# sch_substrate_board_isp.net
KiCad netlist of a schematic drawn in Altium Designer
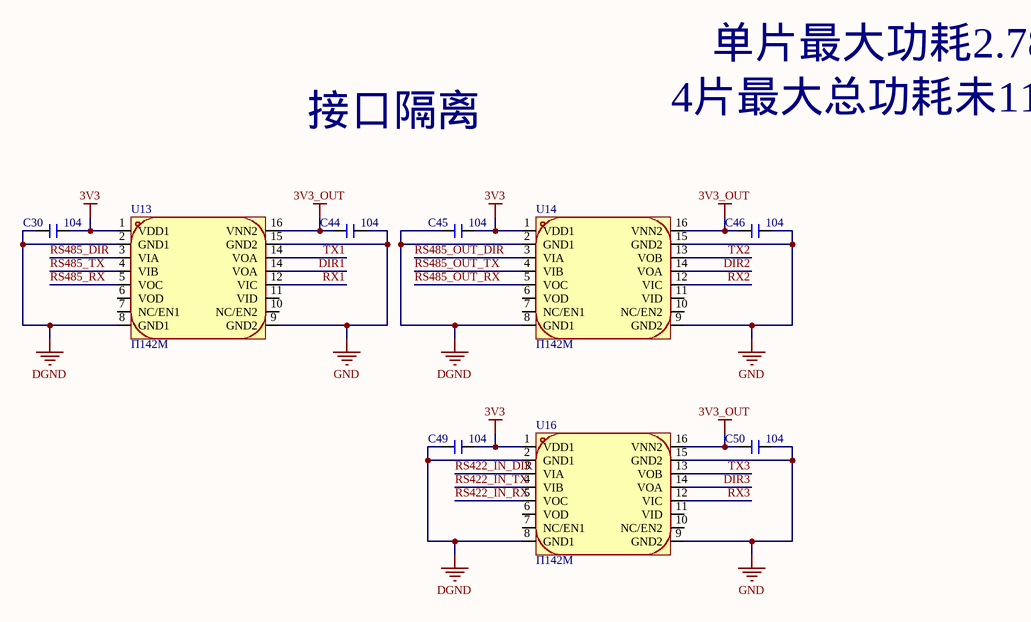
[diagram p0: sch_substrate_board_isp.SchDoc]

(export (version "E")
  (design (tool "Eeschema 10.0.6"))
  (components
    (comp (ref "C30")
      (value "104")
      (footprint "C 0805_L")
      (description "贴片电容")
      (libsource (lib "0.1 - 电阻-电容-电感") (part "C"))
    )
    (comp (ref "C44")
      (value "104")
      (footprint "C 0805_L")
      (description "贴片电容")
      (libsource (lib "0.1 - 电阻-电容-电感") (part "C"))
    )
    (comp (ref "C45")
      (value "104")
      (footprint "C 0805_L")
      (description "贴片电容")
      (libsource (lib "0.1 - 电阻-电容-电感") (part "C"))
    )
    (comp (ref "C46")
      (value "104")
      (footprint "C 0805_L")
      (description "贴片电容")
      (libsource (lib "0.1 - 电阻-电容-电感") (part "C"))
    )
    (comp (ref "C49")
      (value "104")
      (footprint "C 0805_L")
      (description "贴片电容")
      (libsource (lib "0.1 - 电阻-电容-电感") (part "C"))
    )
    (comp (ref "C50")
      (value "104")
      (footprint "C 0805_L")
      (description "贴片电容")
      (libsource (lib "0.1 - 电阻-电容-电感") (part "C"))
    )
    (comp (ref "U13")
      (value "Π142M")
      (footprint "π120M32")
      (description "数字隔离器")
      (libsource (lib "") (part "Π142M_1"))
    )
    (comp (ref "U14")
      (value "Π142M")
      (footprint "π120M32")
      (description "数字隔离器")
      (libsource (lib "schlib_substrate") (part "Π142M"))
    )
    (comp (ref "U16")
      (value "Π142M")
      (footprint "π120M32")
      (description "数字隔离器")
      (libsource (lib "schlib_substrate") (part "Π142M"))
    )
  )
  (nets
    (net (code "1") (name "/DIR1") (class "Default")
      (node (ref "U13") (pin "14") (pinfunction "VOA_14") (pintype "passive"))
    )
    (net (code "2") (name "/DIR2") (class "Default")
      (node (ref "U14") (pin "14") (pinfunction "VOA_14") (pintype "passive"))
    )
    (net (code "3") (name "/DIR3") (class "Default")
      (node (ref "U16") (pin "14") (pinfunction "VOA_14") (pintype "passive"))
    )
    (net (code "4") (name "/RS422_IN_DIR") (class "Default")
      (node (ref "U16") (pin "3") (pinfunction "VIA_3") (pintype "passive"))
    )
    (net (code "5") (name "/RS422_IN_RX") (class "Default")
      (node (ref "U16") (pin "5") (pinfunction "VOC_5") (pintype "passive"))
    )
    (net (code "6") (name "/RS422_IN_TX") (class "Default")
      (node (ref "U16") (pin "4") (pinfunction "VIB_4") (pintype "passive"))
    )
    (net (code "7") (name "/RS485_DIR") (class "Default")
      (node (ref "U13") (pin "3") (pinfunction "VIA_3") (pintype "passive"))
    )
    (net (code "8") (name "/RS485_OUT_DIR") (class "Default")
      (node (ref "U14") (pin "3") (pinfunction "VIA_3") (pintype "passive"))
    )
    (net (code "9") (name "/RS485_OUT_RX") (class "Default")
      (node (ref "U14") (pin "5") (pinfunction "VOC_5") (pintype "passive"))
    )
    (net (code "10") (name "/RS485_OUT_TX") (class "Default")
      (node (ref "U14") (pin "4") (pinfunction "VIB_4") (pintype "passive"))
    )
    (net (code "11") (name "/RS485_RX") (class "Default")
      (node (ref "U13") (pin "5") (pinfunction "VOC_5") (pintype "passive"))
    )
    (net (code "12") (name "/RS485_TX") (class "Default")
      (node (ref "U13") (pin "4") (pinfunction "VIB_4") (pintype "passive"))
    )
    (net (code "13") (name "/RX1") (class "Default")
      (node (ref "U13") (pin "12") (pinfunction "VIC_12") (pintype "passive"))
    )
    (net (code "14") (name "/RX2") (class "Default")
      (node (ref "U14") (pin "12") (pinfunction "VIC_12") (pintype "passive"))
    )
    (net (code "15") (name "/RX3") (class "Default")
      (node (ref "U16") (pin "12") (pinfunction "VIC_12") (pintype "passive"))
    )
    (net (code "16") (name "/TX1") (class "Default")
      (node (ref "U13") (pin "14") (pinfunction "VOA_14") (pintype "passive"))
    )
    (net (code "17") (name "/TX2") (class "Default")
      (node (ref "U14") (pin "13") (pinfunction "VOB_13") (pintype "passive"))
    )
    (net (code "18") (name "/TX3") (class "Default")
      (node (ref "U16") (pin "13") (pinfunction "VOB_13") (pintype "passive"))
    )
    (net (code "19") (name "3V3") (class "Default")
      (node (ref "C30") (pin "1") (pinfunction "1_1") (pintype "passive"))
      (node (ref "C45") (pin "1") (pinfunction "1_1") (pintype "passive"))
      (node (ref "C49") (pin "1") (pinfunction "1_1") (pintype "passive"))
      (node (ref "U13") (pin "1") (pinfunction "VDD1_1") (pintype "passive"))
      (node (ref "U14") (pin "1") (pinfunction "VDD1_1") (pintype "passive"))
      (node (ref "U16") (pin "1") (pinfunction "VDD1_1") (pintype "passive"))
    )
    (net (code "20") (name "3V3_OUT") (class "Default")
      (node (ref "C44") (pin "2") (pinfunction "2_2") (pintype "passive"))
      (node (ref "C46") (pin "2") (pinfunction "2_2") (pintype "passive"))
      (node (ref "C50") (pin "2") (pinfunction "2_2") (pintype "passive"))
      (node (ref "U13") (pin "16") (pinfunction "VNN2_16") (pintype "passive"))
      (node (ref "U14") (pin "16") (pinfunction "VNN2_16") (pintype "passive"))
      (node (ref "U16") (pin "16") (pinfunction "VNN2_16") (pintype "passive"))
    )
    (net (code "21") (name "DGND") (class "Default")
      (node (ref "C30") (pin "2") (pinfunction "2_2") (pintype "passive"))
      (node (ref "C45") (pin "2") (pinfunction "2_2") (pintype "passive"))
      (node (ref "C49") (pin "2") (pinfunction "2_2") (pintype "passive"))
      (node (ref "U13") (pin "2") (pinfunction "GND1_2") (pintype "passive"))
      (node (ref "U13") (pin "8") (pinfunction "GND1_8") (pintype "passive"))
      (node (ref "U14") (pin "2") (pinfunction "GND1_2") (pintype "passive"))
      (node (ref "U14") (pin "8") (pinfunction "GND1_8") (pintype "passive"))
      (node (ref "U16") (pin "2") (pinfunction "GND1_2") (pintype "passive"))
      (node (ref "U16") (pin "8") (pinfunction "GND1_8") (pintype "passive"))
    )
    (net (code "22") (name "GND") (class "Default")
      (node (ref "C44") (pin "1") (pinfunction "1_1") (pintype "passive"))
      (node (ref "C46") (pin "1") (pinfunction "1_1") (pintype "passive"))
      (node (ref "C50") (pin "1") (pinfunction "1_1") (pintype "passive"))
      (node (ref "U13") (pin "15") (pinfunction "GND2_15") (pintype "passive"))
      (node (ref "U13") (pin "9") (pinfunction "GND2_9") (pintype "passive"))
      (node (ref "U14") (pin "15") (pinfunction "GND2_15") (pintype "passive"))
      (node (ref "U14") (pin "9") (pinfunction "GND2_9") (pintype "passive"))
      (node (ref "U16") (pin "15") (pinfunction "GND2_15") (pintype "passive"))
      (node (ref "U16") (pin "9") (pinfunction "GND2_9") (pintype "passive"))
    )
    (net (code "23") (name "unconnected-(U13-NC{slash}EN1-Pad7)") (class "Default")
      (node (ref "U13") (pin "7") (pinfunction "NC/EN1_7") (pintype "passive"))
    )
    (net (code "24") (name "unconnected-(U13-NC{slash}EN2-Pad10)") (class "Default")
      (node (ref "U13") (pin "10") (pinfunction "NC/EN2_10") (pintype "passive"))
    )
    (net (code "25") (name "unconnected-(U13-VID-Pad11)") (class "Default")
      (node (ref "U13") (pin "11") (pinfunction "VID_11") (pintype "passive"))
    )
    (net (code "26") (name "unconnected-(U13-VOD-Pad6)") (class "Default")
      (node (ref "U13") (pin "6") (pinfunction "VOD_6") (pintype "passive"))
    )
    (net (code "27") (name "unconnected-(U14-NC{slash}EN1-Pad7)") (class "Default")
      (node (ref "U14") (pin "7") (pinfunction "NC/EN1_7") (pintype "passive"))
    )
    (net (code "28") (name "unconnected-(U14-NC{slash}EN2-Pad10)") (class "Default")
      (node (ref "U14") (pin "10") (pinfunction "NC/EN2_10") (pintype "passive"))
    )
    (net (code "29") (name "unconnected-(U14-VID-Pad11)") (class "Default")
      (node (ref "U14") (pin "11") (pinfunction "VID_11") (pintype "passive"))
    )
    (net (code "30") (name "unconnected-(U14-VOD-Pad6)") (class "Default")
      (node (ref "U14") (pin "6") (pinfunction "VOD_6") (pintype "passive"))
    )
    (net (code "31") (name "unconnected-(U16-NC{slash}EN1-Pad7)") (class "Default")
      (node (ref "U16") (pin "7") (pinfunction "NC/EN1_7") (pintype "passive"))
    )
    (net (code "32") (name "unconnected-(U16-NC{slash}EN2-Pad10)") (class "Default")
      (node (ref "U16") (pin "10") (pinfunction "NC/EN2_10") (pintype "passive"))
    )
    (net (code "33") (name "unconnected-(U16-VID-Pad11)") (class "Default")
      (node (ref "U16") (pin "11") (pinfunction "VID_11") (pintype "passive"))
    )
    (net (code "34") (name "unconnected-(U16-VOD-Pad6)") (class "Default")
      (node (ref "U16") (pin "6") (pinfunction "VOD_6") (pintype "passive"))
    )
  )
)
